# esp32.net
KiCad netlist of a schematic drawn in Altium Designer
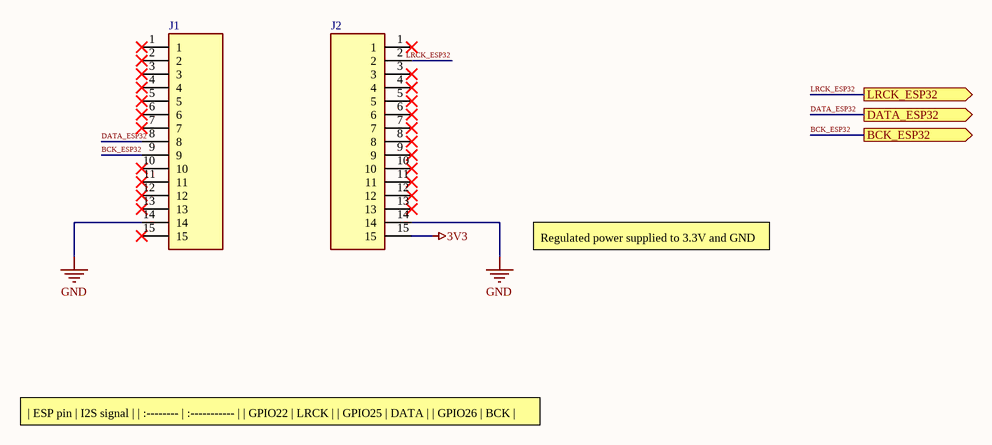
[diagram p0: esp32.SchDoc]

(export (version "E")
  (design (tool "Eeschema 10.0.6"))
  (components
    (comp (ref "J1")
      (value "PPPC151LFBN-RC")
      (footprint "RHDR15W80P0X254_1X15_3860X254X870P")
      (description "CONN HEADER FMALE 15POS .1\" GOLD")
      (fields (field (name "MANUFACTURER") "Sullins"))
      (libsource (lib "project_x_sch_library") (part "PPPC151LFBN-RC"))
    )
    (comp (ref "J2")
      (value "PPPC151LFBN-RC")
      (footprint "RHDR15W80P0X254_1X15_3860X254X870P")
      (description "CONN HEADER FMALE 15POS .1\" GOLD")
      (fields (field (name "MANUFACTURER") "Sullins"))
      (libsource (lib "") (part "PPPC151LFBN-RC_1"))
    )
  )
  (nets
    (net (code "1") (name "/BCK_ESP32") (class "Default")
      (node (ref "J1") (pin "9") (pinfunction "9_9") (pintype "passive"))
    )
    (net (code "2") (name "/DATA_ESP32") (class "Default")
      (node (ref "J1") (pin "8") (pinfunction "8_8") (pintype "passive"))
    )
    (net (code "3") (name "/LRCK_ESP32") (class "Default")
      (node (ref "J2") (pin "2") (pinfunction "2_2") (pintype "passive"))
    )
    (net (code "4") (name "3V3") (class "Default")
      (node (ref "J2") (pin "15") (pinfunction "15_15") (pintype "passive"))
    )
    (net (code "5") (name "GND") (class "Default")
      (node (ref "J1") (pin "14") (pinfunction "14_14") (pintype "passive"))
      (node (ref "J2") (pin "14") (pinfunction "14_14") (pintype "passive"))
    )
    (net (code "6") (name "unconnected-(J1-Pad1)") (class "Default")
      (node (ref "J1") (pin "1") (pinfunction "1_1") (pintype "passive+no_connect"))
    )
    (net (code "7") (name "unconnected-(J1-Pad2)") (class "Default")
      (node (ref "J1") (pin "2") (pinfunction "2_2") (pintype "passive+no_connect"))
    )
    (net (code "8") (name "unconnected-(J1-Pad3)") (class "Default")
      (node (ref "J1") (pin "3") (pinfunction "3_3") (pintype "passive+no_connect"))
    )
    (net (code "9") (name "unconnected-(J1-Pad4)") (class "Default")
      (node (ref "J1") (pin "4") (pinfunction "4_4") (pintype "passive+no_connect"))
    )
    (net (code "10") (name "unconnected-(J1-Pad5)") (class "Default")
      (node (ref "J1") (pin "5") (pinfunction "5_5") (pintype "passive+no_connect"))
    )
    (net (code "11") (name "unconnected-(J1-Pad6)") (class "Default")
      (node (ref "J1") (pin "6") (pinfunction "6_6") (pintype "passive+no_connect"))
    )
    (net (code "12") (name "unconnected-(J1-Pad7)") (class "Default")
      (node (ref "J1") (pin "7") (pinfunction "7_7") (pintype "passive+no_connect"))
    )
    (net (code "13") (name "unconnected-(J1-Pad10)") (class "Default")
      (node (ref "J1") (pin "10") (pinfunction "10_10") (pintype "passive+no_connect"))
    )
    (net (code "14") (name "unconnected-(J1-Pad11)") (class "Default")
      (node (ref "J1") (pin "11") (pinfunction "11_11") (pintype "passive+no_connect"))
    )
    (net (code "15") (name "unconnected-(J1-Pad12)") (class "Default")
      (node (ref "J1") (pin "12") (pinfunction "12_12") (pintype "passive+no_connect"))
    )
    (net (code "16") (name "unconnected-(J1-Pad13)") (class "Default")
      (node (ref "J1") (pin "13") (pinfunction "13_13") (pintype "passive+no_connect"))
    )
    (net (code "17") (name "unconnected-(J1-Pad15)") (class "Default")
      (node (ref "J1") (pin "15") (pinfunction "15_15") (pintype "passive+no_connect"))
    )
    (net (code "18") (name "unconnected-(J2-Pad1)") (class "Default")
      (node (ref "J2") (pin "1") (pinfunction "1_1") (pintype "passive+no_connect"))
    )
    (net (code "19") (name "unconnected-(J2-Pad3)") (class "Default")
      (node (ref "J2") (pin "3") (pinfunction "3_3") (pintype "passive+no_connect"))
    )
    (net (code "20") (name "unconnected-(J2-Pad4)") (class "Default")
      (node (ref "J2") (pin "4") (pinfunction "4_4") (pintype "passive+no_connect"))
    )
    (net (code "21") (name "unconnected-(J2-Pad5)") (class "Default")
      (node (ref "J2") (pin "5") (pinfunction "5_5") (pintype "passive+no_connect"))
    )
    (net (code "22") (name "unconnected-(J2-Pad6)") (class "Default")
      (node (ref "J2") (pin "6") (pinfunction "6_6") (pintype "passive+no_connect"))
    )
    (net (code "23") (name "unconnected-(J2-Pad7)") (class "Default")
      (node (ref "J2") (pin "7") (pinfunction "7_7") (pintype "passive+no_connect"))
    )
    (net (code "24") (name "unconnected-(J2-Pad8)") (class "Default")
      (node (ref "J2") (pin "8") (pinfunction "8_8") (pintype "passive+no_connect"))
    )
    (net (code "25") (name "unconnected-(J2-Pad9)") (class "Default")
      (node (ref "J2") (pin "9") (pinfunction "9_9") (pintype "passive+no_connect"))
    )
    (net (code "26") (name "unconnected-(J2-Pad10)") (class "Default")
      (node (ref "J2") (pin "10") (pinfunction "10_10") (pintype "passive+no_connect"))
    )
    (net (code "27") (name "unconnected-(J2-Pad11)") (class "Default")
      (node (ref "J2") (pin "11") (pinfunction "11_11") (pintype "passive+no_connect"))
    )
    (net (code "28") (name "unconnected-(J2-Pad12)") (class "Default")
      (node (ref "J2") (pin "12") (pinfunction "12_12") (pintype "passive+no_connect"))
    )
    (net (code "29") (name "unconnected-(J2-Pad13)") (class "Default")
      (node (ref "J2") (pin "13") (pinfunction "13_13") (pintype "passive+no_connect"))
    )
  )
)
